# VCU-S03-V00-PSU3V3.net
KiCad netlist of a schematic drawn in Altium Designer
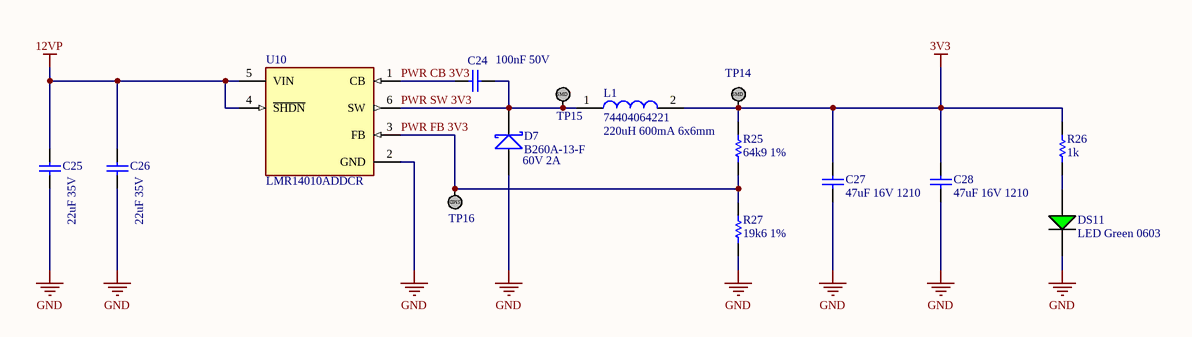
[diagram p0: VCU-S03-V00-PSU3V3.SchDoc]

(export (version "E")
  (design (tool "Eeschema 10.0.6"))
  (components
    (comp (ref "C24")
      (value "100nF 50V")
      (footprint "Cap_Ceramic_0603")
      (description "Capacitor, Ceramic, SMD, 100nF, 50V, 5%, X7R, 0603")
      (libsource (lib "StandardCapacitors") (part "100nF 50V 5% X7R 0603"))
    )
    (comp (ref "C25")
      (value "22uF 35V")
      (footprint "Cap_Ceramic_1206")
      (description "22µF ±20% 35V Ceramic Capacitor X5R 1206 (3216 Metric)")
      (libsource (lib "StandardCapacitors") (part "22uF 35V 20% X5R 1206"))
    )
    (comp (ref "C26")
      (value "22uF 35V")
      (footprint "Cap_Ceramic_1206")
      (description "22µF ±20% 35V Ceramic Capacitor X5R 1206 (3216 Metric)")
      (libsource (lib "StandardCapacitors") (part "22uF 35V 20% X5R 1206"))
    )
    (comp (ref "C27")
      (value "47uF 16V 1210")
      (footprint "Cap_Ceramic_1210")
      (description "Capacitor, Ceramic, SMD, 47uF, 16V, 5%, X7R, 1210")
      (libsource (lib "StandardCapacitors") (part "47uF 16V 10% X7R 1210"))
    )
    (comp (ref "C28")
      (value "47uF 16V 1210")
      (footprint "Cap_Ceramic_1210")
      (description "Capacitor, Ceramic, SMD, 47uF, 16V, 5%, X7R, 1210")
      (libsource (lib "StandardCapacitors") (part "47uF 16V 10% X7R 1210"))
    )
    (comp (ref "D7")
      (value "B260A-13-F")
      (footprint "SMA")
      (description "Diode, Schottky Barrier Rectifier, 60 V, 2 A, B260A-13-F")
      (libsource (lib "QUTMS_DiodeLibrary") (part "B260A-13-F"))
    )
    (comp (ref "DS11")
      (value "LED Green 0603")
      (footprint "LED GREEN 0603")
      (libsource (lib "QUTMS_LEDLibrary") (part "LED Green 0603"))
    )
    (comp (ref "L1")
      (value "74404064221")
      (footprint "Inductor_6x6mm")
      (description "FIXED IND 220UH 660MA 850 MOHM")
      (libsource (lib "QUTMS_InductorLibrary") (part "74404064221"))
    )
    (comp (ref "R25")
      (value "64k9 1%")
      (footprint "Res_ThinFilm_0603")
      (description "Resistor, SMD, 64k9, 0.1W, 5%, 0603")
      (libsource (lib "StandardResistors") (part "64k9 1% 0603"))
    )
    (comp (ref "R26")
      (value "1k")
      (footprint "Res_ThinFilm_0603")
      (description "Resistor, SMD, 1k, 0.1W, 5%, 0603")
      (libsource (lib "StandardResistors") (part "1k 5% 0603"))
    )
    (comp (ref "R27")
      (value "19k6 1%")
      (footprint "Res_ThinFilm_0603")
      (description "Resistor, SMD, 19k6, 0.1W, 5%, 0603")
      (libsource (lib "StandardResistors") (part "19k6 1% 0603"))
    )
    (comp (ref "TP14")
      (value "TestPoint_SMD")
      (footprint "TestPointSMD")
      (libsource (lib "StandardTest") (part "TestPoint_SMD"))
    )
    (comp (ref "TP15")
      (value "TestPoint_SMD")
      (footprint "TestPointSMD")
      (libsource (lib "StandardTest") (part "TestPoint_SMD"))
    )
    (comp (ref "TP16")
      (value "TestPoint_SMD")
      (footprint "TestPointSMD")
      (libsource (lib "StandardTest") (part "TestPoint_SMD"))
    )
    (comp (ref "U10")
      (value "LMR14010ADDCR")
      (footprint "FP-DDC0006A-MFG")
      (description "IC REG BUCK ADJ 1A TSOT23-6")
      (fields
        (field (name "MANUFACTURER") "Texas Instruments")
        (field (name "OCTOPART") "https://octopart.com/lmr14010addcr-texas+instruments-90753290")
      )
      (libsource (lib "Altium Content Vault") (part "248534993f007311ab4e1890f26e637"))
    )
  )
  (nets
    (net (code "1") (name "/PWR CB 3V3") (class "Default")
      (node (ref "C24") (pin "1") (pinfunction "1_1") (pintype "passive"))
      (node (ref "U10") (pin "1") (pinfunction "CB_1") (pintype "input"))
    )
    (net (code "2") (name "/PWR FB 3V3") (class "Default")
      (node (ref "R25") (pin "1") (pinfunction "1_1") (pintype "passive"))
      (node (ref "R27") (pin "2") (pinfunction "2_2") (pintype "passive"))
      (node (ref "TP16") (pin "1") (pinfunction "1_1") (pintype "passive"))
      (node (ref "U10") (pin "3") (pinfunction "FB_3") (pintype "input"))
    )
    (net (code "3") (name "/PWR SW 3V3") (class "Default")
      (node (ref "C24") (pin "2") (pinfunction "2_2") (pintype "passive"))
      (node (ref "D7") (pin "K") (pinfunction "K_K") (pintype "passive"))
      (node (ref "L1") (pin "1") (pinfunction "1_1") (pintype "passive"))
      (node (ref "TP15") (pin "1") (pinfunction "1_1") (pintype "passive"))
      (node (ref "U10") (pin "6") (pinfunction "SW_6") (pintype "output"))
    )
    (net (code "4") (name "3V3") (class "Default")
      (node (ref "C27") (pin "2") (pinfunction "2_2") (pintype "passive"))
      (node (ref "C28") (pin "2") (pinfunction "2_2") (pintype "passive"))
      (node (ref "L1") (pin "2") (pinfunction "2_2") (pintype "passive"))
      (node (ref "R25") (pin "2") (pinfunction "2_2") (pintype "passive"))
      (node (ref "R26") (pin "2") (pinfunction "2_2") (pintype "passive"))
      (node (ref "TP14") (pin "1") (pinfunction "1_1") (pintype "passive"))
    )
    (net (code "5") (name "12VP") (class "Default")
      (node (ref "C25") (pin "2") (pinfunction "2_2") (pintype "passive"))
      (node (ref "C26") (pin "2") (pinfunction "2_2") (pintype "passive"))
      (node (ref "U10") (pin "4") (pinfunction "~{SHDN}_4") (pintype "input"))
      (node (ref "U10") (pin "5") (pinfunction "VIN_5") (pintype "power_in"))
    )
    (net (code "6") (name "GND") (class "Default")
      (node (ref "C25") (pin "1") (pinfunction "1_1") (pintype "passive"))
      (node (ref "C26") (pin "1") (pinfunction "1_1") (pintype "passive"))
      (node (ref "C27") (pin "1") (pinfunction "1_1") (pintype "passive"))
      (node (ref "C28") (pin "1") (pinfunction "1_1") (pintype "passive"))
      (node (ref "D7") (pin "A") (pinfunction "A_A") (pintype "passive"))
      (node (ref "DS11") (pin "2") (pinfunction "C_2") (pintype "passive"))
      (node (ref "R27") (pin "1") (pinfunction "1_1") (pintype "passive"))
      (node (ref "U10") (pin "2") (pinfunction "GND_2") (pintype "power_in"))
    )
    (net (code "7") (name "Net-(DS11-A)") (class "Default")
      (node (ref "DS11") (pin "1") (pinfunction "A_1") (pintype "passive"))
      (node (ref "R26") (pin "1") (pinfunction "1_1") (pintype "passive"))
    )
  )
)
